# pca10059.net
KiCad netlist of a schematic drawn in Altium Designer
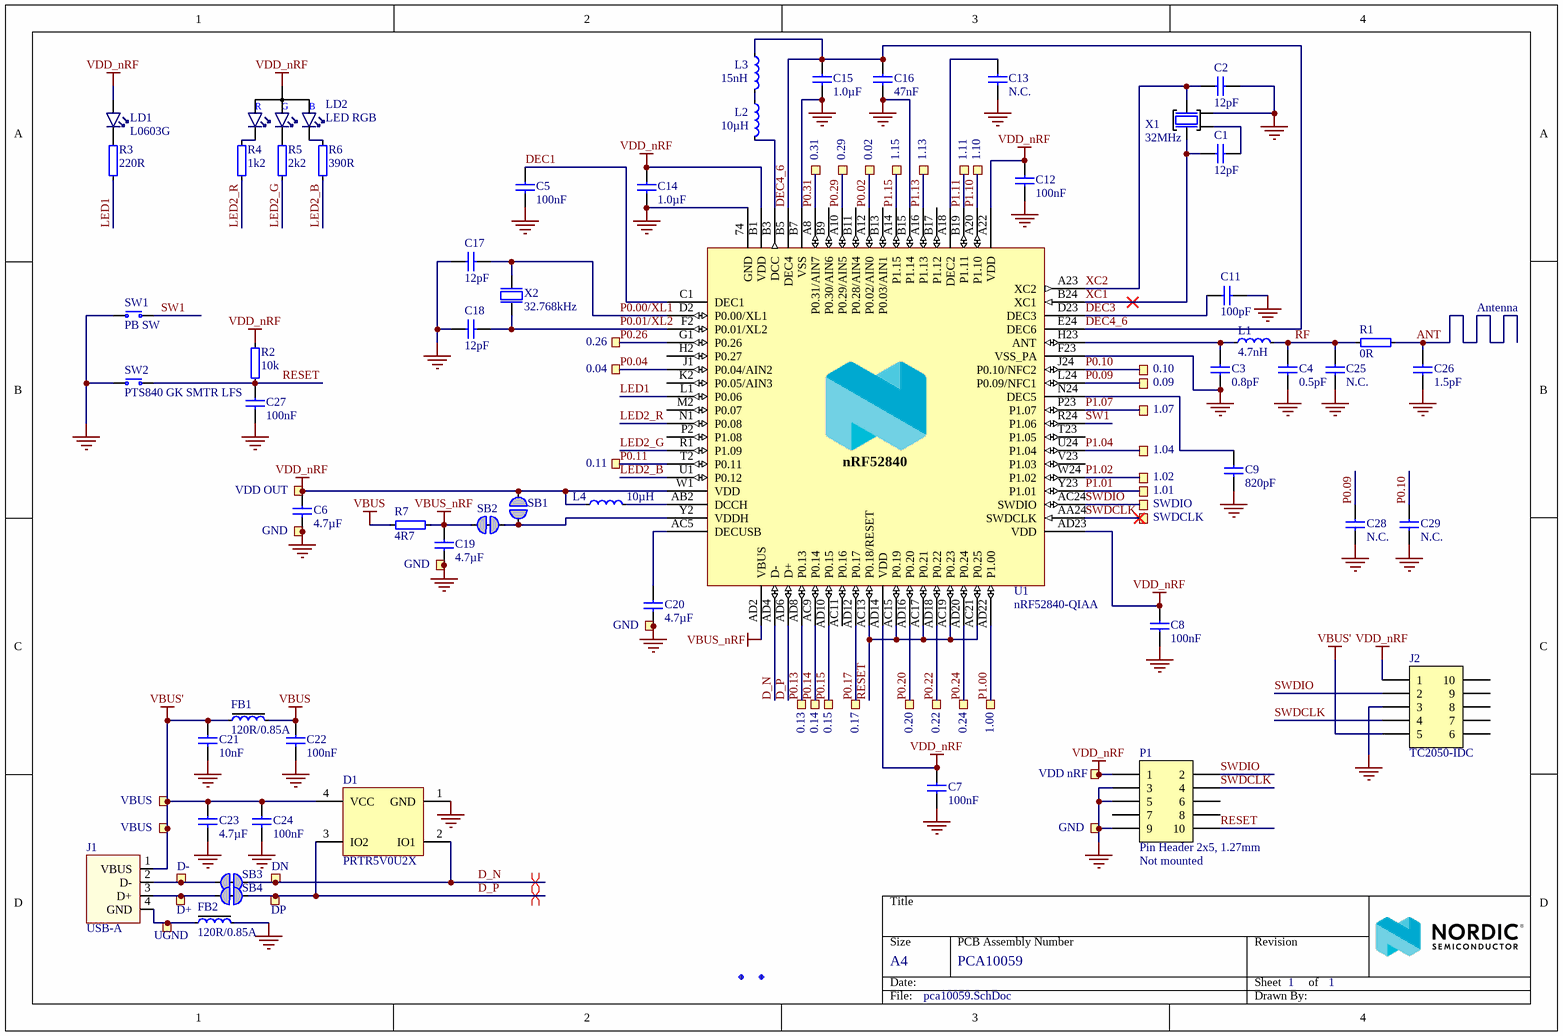
[diagram p0: pca10059.SchDoc]

(export (version "E")
  (design (tool "Eeschema 10.0.6"))
  (components
    (comp (ref "0.02")
      (value "CH")
      (footprint "Castellated_Hole_0.9mm")
      (description "Castellated Hole 0.9mm")
      (fields (field (name "MANUFACTURER") "N.A.") (field (name "AUTHOR") "rsk"))
      (libsource (lib "") (part "TESTPAD_2"))
    )
    (comp (ref "0.04")
      (value "Ø1.0mm,SMD")
      (footprint "TP_SMD_D1.0mm")
      (description "1.0mm circular SMD testpad")
      (fields
        (field (name "PART NUMBER") "TP_SMD_Ø1.0MM")
        (field (name "MANUFACTURER") "Nordic Semiconductor")
        (field (name "AUTHOR") "rsk")
      )
      (libsource (lib "AltiumLib") (part "TESTPAD"))
    )
    (comp (ref "0.09")
      (value "CH")
      (footprint "Castellated_Hole_0.9mm")
      (description "Castellated Hole 0.9mm")
      (fields (field (name "MANUFACTURER") "N.A.") (field (name "AUTHOR") "rsk"))
      (libsource (lib "") (part "TESTPAD_3"))
    )
    (comp (ref "0.10")
      (value "CH")
      (footprint "Castellated_Hole_0.9mm")
      (description "Castellated Hole 0.9mm")
      (fields (field (name "MANUFACTURER") "N.A.") (field (name "AUTHOR") "rsk"))
      (libsource (lib "") (part "TESTPAD_3"))
    )
    (comp (ref "0.11")
      (value "Ø1.0mm,SMD")
      (footprint "TP_SMD_D1.0mm")
      (description "1.0mm circular SMD testpad")
      (fields
        (field (name "PART NUMBER") "TP_SMD_Ø1.0MM")
        (field (name "MANUFACTURER") "Nordic Semiconductor")
        (field (name "AUTHOR") "rsk")
      )
      (libsource (lib "AltiumLib") (part "TESTPAD"))
    )
    (comp (ref "0.13")
      (value "CH")
      (footprint "Castellated_Hole_0.9mm")
      (description "Castellated Hole 0.9mm")
      (fields (field (name "MANUFACTURER") "N.A.") (field (name "AUTHOR") "rsk"))
      (libsource (lib "") (part "TESTPAD_1"))
    )
    (comp (ref "0.14")
      (value "Ø1.0mm,SMD")
      (footprint "TP_SMD_D1.0mm")
      (description "1.0mm circular SMD testpad")
      (fields
        (field (name "PART NUMBER") "TP_SMD_Ø1.0MM")
        (field (name "MANUFACTURER") "Nordic Semiconductor")
        (field (name "AUTHOR") "rsk")
      )
      (libsource (lib "") (part "TESTPAD_1"))
    )
    (comp (ref "0.15")
      (value "CH")
      (footprint "Castellated_Hole_0.9mm")
      (description "Castellated Hole 0.9mm")
      (fields (field (name "MANUFACTURER") "N.A.") (field (name "AUTHOR") "rsk"))
      (libsource (lib "") (part "TESTPAD_1"))
    )
    (comp (ref "0.17")
      (value "CH")
      (footprint "Castellated_Hole_0.9mm")
      (description "Castellated Hole 0.9mm")
      (fields (field (name "MANUFACTURER") "N.A.") (field (name "AUTHOR") "rsk"))
      (libsource (lib "") (part "TESTPAD_1"))
    )
    (comp (ref "0.20")
      (value "CH")
      (footprint "Castellated_Hole_0.9mm")
      (description "Castellated Hole 0.9mm")
      (fields (field (name "MANUFACTURER") "N.A.") (field (name "AUTHOR") "rsk"))
      (libsource (lib "") (part "TESTPAD_1"))
    )
    (comp (ref "0.22")
      (value "CH")
      (footprint "Castellated_Hole_0.9mm")
      (description "Castellated Hole 0.9mm")
      (fields (field (name "MANUFACTURER") "N.A.") (field (name "AUTHOR") "rsk"))
      (libsource (lib "") (part "TESTPAD_1"))
    )
    (comp (ref "0.24")
      (value "CH")
      (footprint "Castellated_Hole_0.9mm")
      (description "Castellated Hole 0.9mm")
      (fields (field (name "MANUFACTURER") "N.A.") (field (name "AUTHOR") "rsk"))
      (libsource (lib "") (part "TESTPAD_1"))
    )
    (comp (ref "0.26")
      (value "Ø1.0mm,SMD")
      (footprint "TP_SMD_D1.0mm")
      (description "1.0mm circular SMD testpad")
      (fields
        (field (name "PART NUMBER") "TP_SMD_Ø1.0MM")
        (field (name "MANUFACTURER") "Nordic Semiconductor")
        (field (name "AUTHOR") "rsk")
      )
      (libsource (lib "AltiumLib") (part "TESTPAD"))
    )
    (comp (ref "0.29")
      (value "CH")
      (footprint "Castellated_Hole_0.9mm")
      (description "Castellated Hole 0.9mm")
      (fields (field (name "MANUFACTURER") "N.A.") (field (name "AUTHOR") "rsk"))
      (libsource (lib "") (part "TESTPAD_2"))
    )
    (comp (ref "0.31")
      (value "CH")
      (footprint "Castellated_Hole_0.9mm")
      (description "Castellated Hole 0.9mm")
      (fields (field (name "MANUFACTURER") "N.A.") (field (name "AUTHOR") "rsk"))
      (libsource (lib "") (part "TESTPAD_2"))
    )
    (comp (ref "1.00")
      (value "CH")
      (footprint "Castellated_Hole_0.9mm")
      (description "Castellated Hole 0.9mm")
      (fields (field (name "MANUFACTURER") "N.A.") (field (name "AUTHOR") "rsk"))
      (libsource (lib "") (part "TESTPAD_1"))
    )
    (comp (ref "1.01")
      (value "Ø1.0mm,SMD")
      (footprint "TP_SMD_D1.0mm")
      (description "1.0mm circular SMD testpad")
      (fields
        (field (name "PART NUMBER") "TP_SMD_Ø1.0MM")
        (field (name "MANUFACTURER") "Nordic Semiconductor")
        (field (name "AUTHOR") "rsk")
      )
      (libsource (lib "") (part "TESTPAD_3"))
    )
    (comp (ref "1.02")
      (value "Ø1.0mm,SMD")
      (footprint "TP_SMD_D1.0mm")
      (description "1.0mm circular SMD testpad")
      (fields
        (field (name "PART NUMBER") "TP_SMD_Ø1.0MM")
        (field (name "MANUFACTURER") "Nordic Semiconductor")
        (field (name "AUTHOR") "rsk")
      )
      (libsource (lib "") (part "TESTPAD_3"))
    )
    (comp (ref "1.04")
      (value "Ø1.0mm,SMD")
      (footprint "TP_SMD_D1.0mm")
      (description "1.0mm circular SMD testpad")
      (fields
        (field (name "PART NUMBER") "TP_SMD_Ø1.0MM")
        (field (name "MANUFACTURER") "Nordic Semiconductor")
        (field (name "AUTHOR") "rsk")
      )
      (libsource (lib "") (part "TESTPAD_3"))
    )
    (comp (ref "1.07")
      (value "Ø1.0mm,SMD")
      (footprint "TP_SMD_D1.0mm")
      (description "1.0mm circular SMD testpad")
      (fields
        (field (name "PART NUMBER") "TP_SMD_Ø1.0MM")
        (field (name "MANUFACTURER") "Nordic Semiconductor")
        (field (name "AUTHOR") "rsk")
      )
      (libsource (lib "") (part "TESTPAD_3"))
    )
    (comp (ref "1.10")
      (value "CH")
      (footprint "Castellated_Hole_0.9mm")
      (description "Castellated Hole 0.9mm")
      (fields (field (name "MANUFACTURER") "N.A.") (field (name "AUTHOR") "rsk"))
      (libsource (lib "") (part "TESTPAD_2"))
    )
    (comp (ref "1.11")
      (value "Ø1.0mm,SMD")
      (footprint "TP_SMD_D1.0mm")
      (description "1.0mm circular SMD testpad")
      (fields
        (field (name "PART NUMBER") "TP_SMD_Ø1.0MM")
        (field (name "MANUFACTURER") "Nordic Semiconductor")
        (field (name "AUTHOR") "rsk")
      )
      (libsource (lib "") (part "TESTPAD_2"))
    )
    (comp (ref "1.13")
      (value "CH")
      (footprint "Castellated_Hole_0.9mm")
      (description "Castellated Hole 0.9mm")
      (fields (field (name "MANUFACTURER") "N.A.") (field (name "AUTHOR") "rsk"))
      (libsource (lib "") (part "TESTPAD_2"))
    )
    (comp (ref "1.15")
      (value "CH")
      (footprint "Castellated_Hole_0.9mm")
      (description "Castellated Hole 0.9mm")
      (fields (field (name "MANUFACTURER") "N.A.") (field (name "AUTHOR") "rsk"))
      (libsource (lib "") (part "TESTPAD_2"))
    )
    (comp (ref "C1")
      (value "12pF")
      (footprint "CAPC0603X03L_C")
      (description "Capacitor, NP0, ±2%")
      (fields
        (field (name "PART NUMBER") "C0201-12p")
        (field (name "MANUFACTURER") "N.A.")
        (field (name "AUTHOR") "rsk")
      )
      (libsource (lib "AltiumLib") (part "CAP"))
    )
    (comp (ref "C2")
      (value "12pF")
      (footprint "CAPC0603X03L_C")
      (description "Capacitor, NP0, ±2%")
      (fields
        (field (name "PART NUMBER") "C0201-12p")
        (field (name "MANUFACTURER") "N.A.")
        (field (name "AUTHOR") "rsk")
      )
      (libsource (lib "AltiumLib") (part "CAP"))
    )
    (comp (ref "C3")
      (value "0.8pF")
      (footprint "CAPC0603X03L_C")
      (description "Capacitor, NP0, ±0.05pF, 50V")
      (fields
        (field (name "PART NUMBER") "C0201-0.8p")
        (field (name "MANUFACTURER") "Murata")
        (field (name "AUTHOR") "rsk")
      )
      (libsource (lib "AltiumLib") (part "CAP"))
    )
    (comp (ref "C4")
      (value "0.5pF")
      (footprint "CAPC0603X03L_C")
      (description "Capacitor, NP0, ±0.05pF")
      (fields
        (field (name "PART NUMBER") "C0201-0.5p")
        (field (name "MANUFACTURER") "N.A.")
        (field (name "AUTHOR") "rsk")
      )
      (libsource (lib "AltiumLib") (part "CAP"))
    )
    (comp (ref "C5")
      (value "100nF")
      (footprint "CAPC0603X03L_C")
      (description "Capacitor, X5R, ±10%")
      (fields
        (field (name "PART NUMBER") "C0201-100n")
        (field (name "MANUFACTURER") "N.A.")
        (field (name "AUTHOR") "rsk")
      )
      (libsource (lib "AltiumLib") (part "CAP"))
    )
    (comp (ref "C6")
      (value "4.7µF")
      (footprint "CAPC1608X06L")
      (description "Capacitor, X5R, ±10%")
      (fields
        (field (name "PART NUMBER") "C0603-4µ7")
        (field (name "MANUFACTURER") "N.A.")
        (field (name "AUTHOR") "rsk")
      )
      (libsource (lib "AltiumLib") (part "CAP"))
    )
    (comp (ref "C7")
      (value "100nF")
      (footprint "CAPC0603X03L_C")
      (description "Capacitor, X5R, ±10%")
      (fields
        (field (name "PART NUMBER") "C0201-100n")
        (field (name "MANUFACTURER") "N.A.")
        (field (name "AUTHOR") "rsk")
      )
      (libsource (lib "AltiumLib") (part "CAP"))
    )
    (comp (ref "C8")
      (value "100nF")
      (footprint "CAPC0603X03L_C")
      (description "Capacitor, X5R, ±10%")
      (fields
        (field (name "PART NUMBER") "C0201-100n")
        (field (name "MANUFACTURER") "N.A.")
        (field (name "AUTHOR") "rsk")
      )
      (libsource (lib "AltiumLib") (part "CAP"))
    )
    (comp (ref "C9")
      (value "820pF")
      (footprint "CAPC0603X03L_C")
      (description "Capacitor, X7R, ±10%")
      (fields
        (field (name "PART NUMBER") "C0201-820p")
        (field (name "MANUFACTURER") "N.A.")
        (field (name "AUTHOR") "rsk")
      )
      (libsource (lib "AltiumLib") (part "CAP"))
    )
    (comp (ref "C11")
      (value "100pF")
      (footprint "CAPC0603X03L_C")
      (description "Capacitor, NP0, ±2%, 25V")
      (fields
        (field (name "PART NUMBER") "C0201-100p")
        (field (name "MANUFACTURER") "Murata")
        (field (name "AUTHOR") "rsk")
      )
      (libsource (lib "AltiumLib") (part "CAP"))
    )
    (comp (ref "C12")
      (value "100nF")
      (footprint "CAPC0603X03L_C")
      (description "Capacitor, X5R, ±10%")
      (fields
        (field (name "PART NUMBER") "C0201-100n")
        (field (name "MANUFACTURER") "N.A.")
        (field (name "AUTHOR") "rsk")
      )
      (libsource (lib "AltiumLib") (part "CAP"))
    )
    (comp (ref "C13")
      (value "N.C.")
      (footprint "CAPC0603X03L_C_NC")
      (description "Not mounted")
      (fields
        (field (name "PART NUMBER") "C0201-N.C.")
        (field (name "MANUFACTURER") "N.A.")
        (field (name "AUTHOR") "rsk")
      )
      (libsource (lib "AltiumLib") (part "CAP"))
    )
    (comp (ref "C14")
      (value "1.0µF")
      (footprint "CAPC1608X06L")
      (description "Capacitor, X7R, ±10%")
      (fields
        (field (name "PART NUMBER") "C0603-1µ0")
        (field (name "MANUFACTURER") "N.A.")
        (field (name "AUTHOR") "rsk")
      )
      (libsource (lib "AltiumLib") (part "CAP"))
    )
    (comp (ref "C15")
      (value "1.0µF")
      (footprint "CAPC1608X06L")
      (description "Capacitor, X7R, ±10%")
      (fields
        (field (name "PART NUMBER") "C0603-1µ0")
        (field (name "MANUFACTURER") "N.A.")
        (field (name "AUTHOR") "rsk")
      )
      (libsource (lib "AltiumLib") (part "CAP"))
    )
    (comp (ref "C16")
      (value "47nF")
      (footprint "CAPC0603X03L_C")
      (description "Capacitor, X5R, ±10%")
      (fields
        (field (name "PART NUMBER") "C0201-47n")
        (field (name "MANUFACTURER") "N.A.")
        (field (name "AUTHOR") "rsk")
      )
      (libsource (lib "AltiumLib") (part "CAP"))
    )
    (comp (ref "C17")
      (value "12pF")
      (footprint "CAPC0603X03L_C")
      (description "Capacitor, NP0, ±2%")
      (fields
        (field (name "PART NUMBER") "C0201-12p")
        (field (name "MANUFACTURER") "N.A.")
        (field (name "AUTHOR") "rsk")
      )
      (libsource (lib "AltiumLib") (part "CAP"))
    )
    (comp (ref "C18")
      (value "12pF")
      (footprint "CAPC0603X03L_C")
      (description "Capacitor, NP0, ±2%")
      (fields
        (field (name "PART NUMBER") "C0201-12p")
        (field (name "MANUFACTURER") "N.A.")
        (field (name "AUTHOR") "rsk")
      )
      (libsource (lib "AltiumLib") (part "CAP"))
    )
    (comp (ref "C19")
      (value "4.7µF")
      (footprint "CAPC1005X04L")
      (description "Capacitor, X5R, ±20%")
      (fields
        (field (name "PART NUMBER") "C0402-4µ7")
        (field (name "MANUFACTURER") "N.A.")
        (field (name "AUTHOR") "rsk")
      )
      (libsource (lib "AltiumLib") (part "CAP"))
    )
    (comp (ref "C20")
      (value "4.7µF")
      (footprint "CAPC1608X06L")
      (description "Capacitor, X5R, ±10%")
      (fields
        (field (name "PART NUMBER") "C0603-4µ7")
        (field (name "MANUFACTURER") "N.A.")
        (field (name "AUTHOR") "rsk")
      )
      (libsource (lib "AltiumLib") (part "CAP"))
    )
    (comp (ref "C21")
      (value "10nF")
      (footprint "CAPC0603X03L_C")
      (description "Capacitor, X7R, ±10%")
      (fields
        (field (name "PART NUMBER") "C0201-10n")
        (field (name "MANUFACTURER") "N.A.")
        (field (name "AUTHOR") "rsk")
      )
      (libsource (lib "AltiumLib") (part "CAP"))
    )
    (comp (ref "C22")
      (value "100nF")
      (footprint "CAPC0603X03L_C")
      (description "Capacitor, X5R, ±10%")
      (fields
        (field (name "PART NUMBER") "C0201-100n")
        (field (name "MANUFACTURER") "N.A.")
        (field (name "AUTHOR") "rsk")
      )
      (libsource (lib "AltiumLib") (part "CAP"))
    )
    (comp (ref "C23")
      (value "4.7µF")
      (footprint "CAPC1005X04L")
      (description "Capacitor, X5R, ±20%")
      (fields
        (field (name "PART NUMBER") "C0402-4µ7")
        (field (name "MANUFACTURER") "N.A.")
        (field (name "AUTHOR") "rsk")
      )
      (libsource (lib "AltiumLib") (part "CAP"))
    )
    (comp (ref "C24")
      (value "100nF")
      (footprint "CAPC0603X03L_C")
      (description "Capacitor, X5R, ±10%")
      (fields
        (field (name "PART NUMBER") "C0201-100n")
        (field (name "MANUFACTURER") "N.A.")
        (field (name "AUTHOR") "rsk")
      )
      (libsource (lib "AltiumLib") (part "CAP"))
    )
    (comp (ref "C25")
      (value "N.C.")
      (footprint "CAPC0603X03L_C_NC")
      (description "Not mounted")
      (fields
        (field (name "PART NUMBER") "C0201-N.C.")
        (field (name "MANUFACTURER") "N.A.")
        (field (name "AUTHOR") "rsk")
      )
      (libsource (lib "AltiumLib") (part "CAP"))
    )
    (comp (ref "C26")
      (value "1.5pF")
      (footprint "CAPC0603X03L_C")
      (description "Capacitor, NP0, ±0.1pF")
      (fields
        (field (name "PART NUMBER") "C0201-1.5p")
        (field (name "MANUFACTURER") "N.A.")
        (field (name "AUTHOR") "rsk")
      )
      (libsource (lib "AltiumLib") (part "CAP"))
    )
    (comp (ref "C27")
      (value "100nF")
      (footprint "CAPC0603X03L_C")
      (description "Capacitor, X5R, ±10%")
      (fields
        (field (name "PART NUMBER") "C0201-100n")
        (field (name "MANUFACTURER") "N.A.")
        (field (name "AUTHOR") "rsk")
      )
      (libsource (lib "AltiumLib") (part "CAP"))
    )
    (comp (ref "C28")
      (value "N.C.")
      (footprint "CAPC1005X04L_NC")
      (description "Not mounted")
      (fields
        (field (name "PART NUMBER") "C0402-N.C.")
        (field (name "MANUFACTURER") "N.A.")
        (field (name "AUTHOR") "rsk")
      )
      (libsource (lib "AltiumLib") (part "CAP"))
    )
    (comp (ref "C29")
      (value "N.C.")
      (footprint "CAPC1005X04L_NC")
      (description "Not mounted")
      (fields
        (field (name "PART NUMBER") "C0402-N.C.")
        (field (name "MANUFACTURER") "N.A.")
        (field (name "AUTHOR") "rsk")
      )
      (libsource (lib "AltiumLib") (part "CAP"))
    )
    (comp (ref "D+")
      (value "Ø1.0mm,SMD")
      (footprint "TP_SMD_D1.0mm")
      (description "1.0mm circular SMD testpad")
      (fields
        (field (name "PART NUMBER") "TP_SMD_Ø1.0MM")
        (field (name "MANUFACTURER") "Nordic Semiconductor")
        (field (name "AUTHOR") "rsk")
      )
      (libsource (lib "") (part "TESTPAD_1"))
    )
    (comp (ref "D-")
      (value "Ø1.0mm,SMD")
      (footprint "TP_SMD_D1.0mm")
      (description "1.0mm circular SMD testpad")
      (fields
        (field (name "PART NUMBER") "TP_SMD_Ø1.0MM")
        (field (name "MANUFACTURER") "Nordic Semiconductor")
        (field (name "AUTHOR") "rsk")
      )
      (libsource (lib "") (part "TESTPAD_2"))
    )
    (comp (ref "D1")
      (value "PRTR5V0U2X")
      (footprint "SOT190P230X110-4L")
      (description "Ultra low capacitance double rail-to-rail ESD protection diode")
      (fields (field (name "MANUFACTURER") "NXP Semiconductors") (field (name "AUTHOR") "rsk"))
      (libsource (lib "AltiumLib") (part "PRTR5V0U2X"))
    )
    (comp (ref "DN")
      (value "Ø1.0mm,SMD")
      (footprint "TP_SMD_D1.0mm")
      (description "1.0mm circular SMD testpad")
      (fields
        (field (name "PART NUMBER") "TP_SMD_Ø1.0MM")
        (field (name "MANUFACTURER") "Nordic Semiconductor")
        (field (name "AUTHOR") "rsk")
      )
      (libsource (lib "") (part "TESTPAD_2"))
    )
    (comp (ref "DP")
      (value "Ø1.0mm,SMD")
      (footprint "TP_SMD_D1.0mm")
      (description "1.0mm circular SMD testpad")
      (fields
        (field (name "PART NUMBER") "TP_SMD_Ø1.0MM")
        (field (name "MANUFACTURER") "Nordic Semiconductor")
        (field (name "AUTHOR") "rsk")
      )
      (libsource (lib "") (part "TESTPAD_1"))
    )
    (comp (ref "FB1")
      (value "120R/0.85A")
      (footprint "INDC0603X03L_C")
      (description "Ferrite Bead, 120 Ohm @ 100MHz, 850mA, 150 mOhm Max")
      (fields
        (field (name "PART NUMBER") "FB0201-120R@100M-850mA")
        (field (name "MANUFACTURER") "Taiyo Yuden")
        (field (name "AUTHOR") "rsk")
      )
      (libsource (lib "AltiumLib") (part "IND_F"))
    )
    (comp (ref "FB2")
      (value "120R/0.85A")
      (footprint "INDC0603X03L_C")
      (description "Ferrite Bead, 120 Ohm @ 100MHz, 850mA, 150 mOhm Max")
      (fields
        (field (name "PART NUMBER") "FB0201-120R@100M-850mA")
        (field (name "MANUFACTURER") "Taiyo Yuden")
        (field (name "AUTHOR") "rsk")
      )
      (libsource (lib "AltiumLib") (part "IND_F"))
    )
    (comp (ref "Fid1")
      (value "Fiducial mark")
      (footprint "Fiducial_Square")
      (description "Fiducial Mark")
      (fields
        (field (name "PART NUMBER") "Fid-Mark-Square")
        (field (name "MANUFACTURER") "N.A.")
        (field (name "AUTHOR") "rsk")
      )
      (libsource (lib "AltiumLib") (part "Fiducial"))
    )
    (comp (ref "Fid2")
      (value "Fiducial mark")
      (footprint "Fiducial")
      (description "Fiducial Mark")
      (fields
        (field (name "PART NUMBER") "Fid-Mark")
        (field (name "MANUFACTURER") "N.A.")
        (field (name "AUTHOR") "rsk")
      )
      (libsource (lib "AltiumLib") (part "Fiducial"))
    )
    (comp (ref "GND1")
      (value "GND")
      (footprint "Castellated_Hole_0.9mm")
      (description "Castellated Hole 0.9mm")
      (fields (field (name "MANUFACTURER") "N.A.") (field (name "AUTHOR") "rsk"))
      (libsource (lib "AltiumLib") (part "TESTPAD"))
    )
    (comp (ref "GND2")
      (value "GND")
      (footprint "Castellated_Hole_0.9mm_S")
      (description "Castellated Hole 0.9mm")
      (fields
        (field (name "PART NUMBER") "Castellated Hole 0.9mm_S")
        (field (name "MANUFACTURER") "N.A.")
        (field (name "AUTHOR") "rsk")
      )
      (libsource (lib "AltiumLib") (part "TESTPAD"))
    )
    (comp (ref "GND3")
      (value "GND")
      (footprint "Castellated_Hole_0.9mm_S")
      (description "Castellated Hole 0.9mm")
      (fields
        (field (name "PART NUMBER") "Castellated Hole 0.9mm_S")
        (field (name "MANUFACTURER") "N.A.")
        (field (name "AUTHOR") "rsk")
      )
      (libsource (lib "AltiumLib") (part "TESTPAD"))
    )
    (comp (ref "GND4")
      (value "GND")
      (footprint "TP_SMD_D1.0mm")
      (description "1.0mm circular SMD testpad")
      (fields
        (field (name "PART NUMBER") "TP_SMD_Ø1.0MM")
        (field (name "MANUFACTURER") "Nordic Semiconductor")
        (field (name "AUTHOR") "rsk")
      )
      (libsource (lib "AltiumLib") (part "TESTPAD"))
    )
    (comp (ref "J1")
      (value "USB-A")
      (footprint "USB-A-PCB")
      (description "USB-A PCB footprint")
      (fields
        (field (name "PART NUMBER") "USB-A-PCB")
        (field (name "MANUFACTURER") "N.A.")
        (field (name "AUTHOR") "rsk")
      )
      (libsource (lib "AltiumLib") (part "USB-PCB-A"))
    )
    (comp (ref "J2")
      (value "TC2050-IDC")
      (footprint "TC2050-IDC-NLFP")
      (description "CBL PLUG-OF-NAILS 10-PIN")
      (fields
        (field (name "PART NUMBER") "TC2050-IDC-NLFP")
        (field (name "MANUFACTURER") "Tag-Connect LLC")
        (field (name "AUTHOR") "rsk")
      )
      (libsource (lib "AltiumLib") (part "CONN-2x5_var2_No_BOM"))
    )
    (comp (ref "L1")
      (value "4.7nH")
      (footprint "INDC0603X03L_C")
      (description "Inductor, 350mA, ±3%")
      (fields
        (field (name "PART NUMBER") "L0201-4n7")
        (field (name "MANUFACTURER") "Murata")
        (field (name "AUTHOR") "rsk")
      )
      (libsource (lib "AltiumLib") (part "IND"))
    )
    (comp (ref "L2")
      (value "10µH")
      (footprint "INDC1608X06L")
      (description "Inductor, 80mA, ±10%")
      (fields
        (field (name "PART NUMBER") "L0603-10µ")
        (field (name "MANUFACTURER") "Taiyo Yuden")
        (field (name "AUTHOR") "rsk")
      )
      (libsource (lib "AltiumLib") (part "IND"))
    )
    (comp (ref "L3")
      (value "15nH")
      (footprint "INDC1005X04L")
      (description "Inductor, 320mA, ±5%")
      (fields
        (field (name "PART NUMBER") "L0402-15n")
        (field (name "MANUFACTURER") "Taiyo Yuden")
        (field (name "AUTHOR") "rsk")
      )
      (libsource (lib "AltiumLib") (part "IND"))
    )
    (comp (ref "L4")
      (value "10µH")
      (footprint "INDC1608X06L")
      (description "Inductor, 80mA, ±10%")
      (fields
        (field (name "PART NUMBER") "L0603-10µ")
        (field (name "MANUFACTURER") "Taiyo Yuden")
        (field (name "AUTHOR") "rsk")
      )
      (libsource (lib "AltiumLib") (part "IND"))
    )
    (comp (ref "LD1")
      (value "L0603G")
      (footprint "LED_0603_G")
      (description "LED, Green, 0603, 573nm, Vf=2.0V, 24mcd, - 40 to +85°C")
      (fields
        (field (name "PART NUMBER") "VS 25C7M5")
        (field (name "MANUFACTURER") "Victory Electronics")
        (field (name "AUTHOR") "rsk")
      )
      (libsource (lib "AltiumLib") (part "D{colon}LED"))
    )
    (comp (ref "LD2")
      (value "LED RGB")
      (footprint "LED_RGB_0603")
      (description "RGB LED 1.60 mm x 0.80 mm SMD")
      (fields
        (field (name "PART NUMBER") "APHF1608LSEEQBDZGKC")
        (field (name "MANUFACTURER") "Kingbright Company LLC")
        (field (name "AUTHOR") "rsk")
      )
      (libsource (lib "AltiumLib") (part "D{colon}LED_RGB"))
    )
    (comp (ref "P1")
      (value "Pin Header 2x5, 1.27mm")
      (footprint "HDR_2x5-SMD-1.27mm-NC")
      (description "Pin Header 2x5, 1.27mm (50mil), SMD, Keying Shroud")
      (fields
        (field (name "PART NUMBER") "Pin Header 2x5 SMD, 1.27mm, KS, N.C.")
        (field (name "ASSEMBLY") "Not mounted")
        (field (name "MANUFACTURER") "W-CON")
        (field (name "AUTHOR") "rsk")
      )
      (libsource (lib "AltiumLib") (part "CONN-2x5"))
    )
    (comp (ref "R1")
      (value "0R")
      (footprint "RESC0603X03L_C")
      (description "Resistor, ±5%, 0.05W")
      (fields
        (field (name "PART NUMBER") "R0201-0R")
        (field (name "MANUFACTURER") "N.A.")
        (field (name "AUTHOR") "rsk")
      )
      (libsource (lib "AltiumLib") (part "RES"))
    )
    (comp (ref "R2")
      (value "10k")
      (footprint "RESC0603X03L_C")
      (description "Resistor, ±1%, 0.05W")
      (fields
        (field (name "PART NUMBER") "R0201-10k")
        (field (name "MANUFACTURER") "N.A.")
        (field (name "AUTHOR") "rsk")
      )
      (libsource (lib "AltiumLib") (part "RES"))
    )
    (comp (ref "R3")
      (value "220R")
      (footprint "RESC0603X03L_C")
      (description "Resistor, ±1%, 0.05W")
      (fields
        (field (name "PART NUMBER") "R0201-220")
        (field (name "MANUFACTURER") "N.A.")
        (field (name "AUTHOR") "rsk")
      )
      (libsource (lib "AltiumLib") (part "RES"))
    )
    (comp (ref "R4")
      (value "1k2")
      (footprint "RESC0603X03L_C")
      (description "Resistor, ±1%, 0.05W")
      (fields
        (field (name "PART NUMBER") "R0201-1k2")
        (field (name "MANUFACTURER") "N.A.")
        (field (name "AUTHOR") "rsk")
      )
      (libsource (lib "AltiumLib") (part "RES"))
    )
    (comp (ref "R5")
      (value "2k2")
      (footprint "RESC0603X03L_C")
      (description "Resistor, ±1%, 0.05W")
      (fields
        (field (name "PART NUMBER") "R0201-2k2")
        (field (name "MANUFACTURER") "N.A.")
        (field (name "AUTHOR") "rsk")
      )
      (libsource (lib "AltiumLib") (part "RES"))
    )
    (comp (ref "R6")
      (value "390R")
      (footprint "RESC0603X03L_C")
      (description "Resistor, ±1%, 0.05W")
      (fields
        (field (name "PART NUMBER") "R0201-390")
        (field (name "MANUFACTURER") "N.A.")
        (field (name "AUTHOR") "rsk")
      )
      (libsource (lib "AltiumLib") (part "RES"))
    )
    (comp (ref "R7")
      (value "4R7")
      (footprint "RESC0603X03L_C")
      (description "Resistor, ±1%, 0.05W")
      (fields
        (field (name "PART NUMBER") "R0201-4R7")
        (field (name "MANUFACTURER") "N.A.")
        (field (name "AUTHOR") "rsk")
      )
      (libsource (lib "AltiumLib") (part "RES"))
    )
    (comp (ref "SB1")
      (value "Solderbridge")
      (footprint "Solderbridge")
      (fields (field (name "MANUFACTURER") "N.A.") (field (name "AUTHOR") "rsk"))
      (libsource (lib "AltiumLib") (part "SOLDERBRIDGE"))
    )
    (comp (ref "SB2")
      (value "Solderbridge")
      (footprint "Solderbridge_Shorted")
      (description "Shorted Solderbridge")
      (fields
        (field (name "PART NUMBER") "Solderbridge Shorted")
        (field (name "MANUFACTURER") "N.A.")
        (field (name "AUTHOR") "rsk")
      )
      (libsource (lib "AltiumLib") (part "SOLDERBRIDGE_SHORTED"))
    )
    (comp (ref "SB3")
      (value "Solderbridge")
      (footprint "Solderbridge_Shorted")
      (description "Shorted Solderbridge")
      (fields
        (field (name "PART NUMBER") "Solderbridge Shorted")
        (field (name "MANUFACTURER") "N.A.")
        (field (name "AUTHOR") "rsk")
      )
      (libsource (lib "AltiumLib") (part "SOLDERBRIDGE_SHORTED"))
    )
    (comp (ref "SB4")
      (value "Solderbridge")
      (footprint "Solderbridge_Shorted")
      (description "Shorted Solderbridge")
      (fields
        (field (name "PART NUMBER") "Solderbridge Shorted")
        (field (name "MANUFACTURER") "N.A.")
        (field (name "AUTHOR") "rsk")
      )
      (libsource (lib "AltiumLib") (part "SOLDERBRIDGE_SHORTED"))
    )
    (comp (ref "SW1")
      (value "PB SW")
      (footprint "C&K_PTS810")
      (description "Tactile Switch, SPNO, SMD, 260gf, 4.2x3.2x2.5mm")
      (fields
        (field (name "PART NUMBER") "PTS810 SJK 250 SMTR LFS")
        (field (name "MANUFACTURER") "C&K")
        (field (name "AUTHOR") "rsk")
      )
      (libsource (lib "AltiumLib") (part "SW-PB"))
    )
    (comp (ref "SW2")
      (value "PTS840 GK SMTR LFS")
      (footprint "EVQP7A_J_B_K")
      (description "Microminiature SMT Switch, Side Actuated")
      (fields (field (name "MANUFACTURER") "C&K") (field (name "AUTHOR") "rsk"))
      (libsource (lib "AltiumLib") (part "SW-PB"))
    )
    (comp (ref "SWDCLK")
      (value "CH")
      (footprint "Castellated_Hole_0.9mm_D")
      (description "Castellated Hole 0.9mm")
      (fields
        (field (name "PART NUMBER") "Castellated Hole 0.9mm_D")
        (field (name "MANUFACTURER") "N.A.")
        (field (name "AUTHOR") "rsk")
      )
      (libsource (lib "") (part "TESTPAD_3"))
    )
    (comp (ref "SWDIO")
      (value "CH")
      (footprint "Castellated_Hole_0.9mm_D")
      (description "Castellated Hole 0.9mm")
      (fields
        (field (name "PART NUMBER") "Castellated Hole 0.9mm_D")
        (field (name "MANUFACTURER") "N.A.")
        (field (name "AUTHOR") "rsk")
      )
      (libsource (lib "") (part "TESTPAD_3"))
    )
    (comp (ref "U1")
      (value "nRF52840-QIAA")
      (footprint "AQFN50P700X700X85_HS-74N")
      (description "Multi-protocol Bluetooth Low Energy, IEEE 802.15.4, ANT and 2.4GHz proprietary system-on-chip")
      (fields
        (field (name "PART NUMBER") "nRF52840-QIAAF0")
        (field (name "MANUFACTURER") "Nordic Semiconductor")
        (field (name "AUTHOR") "hany")
      )
      (libsource (lib "AltiumLib") (part "nRF52840_QIAA"))
    )
    (comp (ref "UGND")
      (value "Ø1.0mm,SMD")
      (footprint "TP_SMD_D1.0mm")
      (description "1.0mm circular SMD testpad")
      (fields
        (field (name "PART NUMBER") "TP_SMD_Ø1.0MM")
        (field (name "MANUFACTURER") "Nordic Semiconductor")
        (field (name "AUTHOR") "rsk")
      )
      (libsource (lib "") (part "TESTPAD_1"))
    )
    (comp (ref "VBUS1")
      (value "VBUS")
      (footprint "Castellated_Hole_0.9mm")
      (description "Castellated Hole 0.9mm")
      (fields (field (name "MANUFACTURER") "N.A.") (field (name "AUTHOR") "rsk"))
      (libsource (lib "AltiumLib") (part "TESTPAD"))
    )
    (comp (ref "VBUS2")
      (value "VBUS")
      (footprint "TP_SMD_D1.0mm")
      (description "1.0mm circular SMD testpad")
      (fields
        (field (name "PART NUMBER") "TP_SMD_Ø1.0MM")
        (field (name "MANUFACTURER") "Nordic Semiconductor")
        (field (name "AUTHOR") "rsk")
      )
      (libsource (lib "AltiumLib") (part "TESTPAD"))
    )
    (comp (ref "VDD nRF")
      (value "Ø1.0mm,SMD")
      (footprint "TP_SMD_D1.0mm")
      (description "1.0mm circular SMD testpad")
      (fields
        (field (name "PART NUMBER") "TP_SMD_Ø1.0MM")
        (field (name "MANUFACTURER") "Nordic Semiconductor")
        (field (name "AUTHOR") "rsk")
      )
      (libsource (lib "AltiumLib") (part "TESTPAD"))
    )
    (comp (ref "VDD OUT")
      (value "CH")
      (footprint "Castellated_Hole_0.9mm")
      (description "Castellated Hole 0.9mm")
      (fields (field (name "MANUFACTURER") "N.A.") (field (name "AUTHOR") "rsk"))
      (libsource (lib "AltiumLib") (part "TESTPAD"))
    )
    (comp (ref "X1")
      (value "32MHz")
      (footprint "BT-XTAL_2016")
      (description "XTAL SMD 2016, 32MHz, Cl=8pF, Tol: ±10ppm, Stab: ±10ppm")
      (fields
        (field (name "PART NUMBER") "XTAL_SMD2016_32MHz_8pF_Murata")
        (field (name "MANUFACTURER") "Murata")
        (field (name "AUTHOR") "rsk")
      )
      (libsource (lib "AltiumLib") (part "XTAL_4-pin"))
    )
    (comp (ref "X2")
      (value "32.768kHz")
      (footprint "XTAL_2012")
      (description "XTAL SMD 2012, 32.768kHz, 9pF, ±20ppm")
      (fields
        (field (name "PART NUMBER") "XTAL_SMD2012_32.768kHz_9pF_Seiko")
        (field (name "MANUFACTURER") "Seiko Instruments")
        (field (name "AUTHOR") "rsk")
      )
      (libsource (lib "AltiumLib") (part "XTAL_2-pin"))
    )
  )
  (nets
    (net (code "1") (name "/ANT") (class "Default")
      (node (ref "C26") (pin "2") (pinfunction "2_2") (pintype "passive"))
      (node (ref "R1") (pin "2") (pinfunction "2_2") (pintype "passive"))
    )
    (net (code "2") (name "/DEC1") (class "Default")
      (node (ref "C5") (pin "1") (pinfunction "1_1") (pintype "passive"))
      (node (ref "U1") (pin "C1") (pinfunction "DEC1_C1") (pintype "power_in"))
    )
    (net (code "3") (name "/DEC3") (class "Default")
      (node (ref "C11") (pin "1") (pinfunction "1_1") (pintype "passive"))
      (node (ref "U1") (pin "D23") (pinfunction "DEC3_D23") (pintype "power_in"))
    )
    (net (code "4") (name "/DEC4_6") (class "Default")
      (node (ref "C15") (pin "2") (pinfunction "2_2") (pintype "passive"))
      (node (ref "C16") (pin "1") (pinfunction "1_1") (pintype "passive"))
      (node (ref "L3") (pin "1") (pinfunction "1_1") (pintype "passive"))
      (node (ref "U1") (pin "B5") (pinfunction "DEC4_B5") (pintype "power_in"))
      (node (ref "U1") (pin "E24") (pinfunction "DEC6_E24") (pintype "power_in"))
    )
    (net (code "5") (name "/D_N") (class "Default")
      (node (ref "D1") (pin "2") (pinfunction "IO1_2") (pintype "passive"))
      (node (ref "DN") (pin "1") (pinfunction "1_1") (pintype "passive"))
      (node (ref "SB3") (pin "1") (pinfunction "0_1") (pintype "passive"))
      (node (ref "U1") (pin "AD4") (pinfunction "D-_AD4") (pintype "bidirectional"))
    )
    (net (code "6") (name "/D_P") (class "Default")
      (node (ref "D1") (pin "3") (pinfunction "IO2_3") (pintype "passive"))
      (node (ref "DP") (pin "1") (pinfunction "1_1") (pintype "passive"))
      (node (ref "SB4") (pin "1") (pinfunction "0_1") (pintype "passive"))
      (node (ref "U1") (pin "AD6") (pinfunction "D+_AD6") (pintype "bidirectional"))
    )
    (net (code "7") (name "/LED1") (class "Default")
      (node (ref "R3") (pin "1") (pinfunction "1_1") (pintype "passive"))
      (node (ref "U1") (pin "L1") (pinfunction "P0.06_L1") (pintype "bidirectional"))
    )
    (net (code "8") (name "/LED2_B") (class "Default")
      (node (ref "R6") (pin "1") (pinfunction "1_1") (pintype "passive"))
      (node (ref "U1") (pin "U1") (pinfunction "P0.12_U1") (pintype "bidirectional"))
    )
    (net (code "9") (name "/LED2_G") (class "Default")
      (node (ref "R5") (pin "1") (pinfunction "1_1") (pintype "passive"))
      (node (ref "U1") (pin "R1") (pinfunction "P1.09_R1") (pintype "bidirectional"))
    )
    (net (code "10") (name "/LED2_R") (class "Default")
      (node (ref "R4") (pin "1") (pinfunction "1_1") (pintype "passive"))
      (node (ref "U1") (pin "N1") (pinfunction "P0.08_N1") (pintype "bidirectional"))
    )
    (net (code "11") (name "/P0.00{slash}XL1") (class "Default")
      (node (ref "C17") (pin "1") (pinfunction "1_1") (pintype "passive"))
      (node (ref "U1") (pin "D2") (pinfunction "P0.00/XL1_D2") (pintype "bidirectional"))
      (node (ref "X2") (pin "1") (pinfunction "inp_1") (pintype "passive"))
    )
    (net (code "12") (name "/P0.01{slash}XL2") (class "Default")
      (node (ref "C18") (pin "1") (pinfunction "1_1") (pintype "passive"))
      (node (ref "U1") (pin "F2") (pinfunction "P0.01/XL2_F2") (pintype "bidirectional"))
      (node (ref "X2") (pin "2") (pinfunction "out_2") (pintype "passive"))
    )
    (net (code "13") (name "/P0.02") (class "Default")
      (node (ref "0.02") (pin "1") (pinfunction "1_1") (pintype "passive"))
      (node (ref "U1") (pin "A12") (pinfunction "P0.02/AIN0_A12") (pintype "bidirectional"))
    )
    (net (code "14") (name "/P0.04") (class "Default")
      (node (ref "0.04") (pin "1") (pinfunction "1_1") (pintype "passive"))
      (node (ref "U1") (pin "J1") (pinfunction "P0.04/AIN2_J1") (pintype "bidirectional"))
    )
    (net (code "15") (name "/P0.09") (class "Default")
      (node (ref "0.09") (pin "1") (pinfunction "1_1") (pintype "passive"))
      (node (ref "C28") (pin "2") (pinfunction "2_2") (pintype "passive"))
      (node (ref "U1") (pin "L24") (pinfunction "P0.09/NFC1_L24") (pintype "bidirectional"))
    )
    (net (code "16") (name "/P0.10") (class "Default")
      (node (ref "0.10") (pin "1") (pinfunction "1_1") (pintype "passive"))
      (node (ref "C29") (pin "1") (pinfunction "1_1") (pintype "passive"))
      (node (ref "U1") (pin "J24") (pinfunction "P0.10/NFC2_J24") (pintype "bidirectional"))
    )
    (net (code "17") (name "/P0.11") (class "Default")
      (node (ref "0.11") (pin "1") (pinfunction "1_1") (pintype "passive"))
      (node (ref "U1") (pin "T2") (pinfunction "P0.11_T2") (pintype "bidirectional"))
    )
    (net (code "18") (name "/P0.13") (class "Default")
      (node (ref "0.13") (pin "1") (pinfunction "1_1") (pintype "passive"))
      (node (ref "U1") (pin "AD8") (pinfunction "P0.13_AD8") (pintype "bidirectional"))
    )
    (net (code "19") (name "/P0.14") (class "Default")
      (node (ref "0.14") (pin "1") (pinfunction "1_1") (pintype "passive"))
      (node (ref "U1") (pin "AC9") (pinfunction "P0.14_AC9") (pintype "bidirectional"))
    )
    (net (code "20") (name "/P0.15") (class "Default")
      (node (ref "0.15") (pin "1") (pinfunction "1_1") (pintype "passive"))
      (node (ref "U1") (pin "AD10") (pinfunction "P0.15_AD10") (pintype "bidirectional"))
    )
    (net (code "21") (name "/P0.17") (class "Default")
      (node (ref "0.17") (pin "1") (pinfunction "1_1") (pintype "passive"))
      (node (ref "U1") (pin "AD12") (pinfunction "P0.17_AD12") (pintype "bidirectional"))
    )
    (net (code "22") (name "/P0.20") (class "Default")
      (node (ref "0.20") (pin "1") (pinfunction "1_1") (pintype "passive"))
      (node (ref "U1") (pin "AD16") (pinfunction "P0.20_AD16") (pintype "bidirectional"))
    )
    (net (code "23") (name "/P0.22") (class "Default")
      (node (ref "0.22") (pin "1") (pinfunction "1_1") (pintype "passive"))
      (node (ref "U1") (pin "AD18") (pinfunction "P0.22_AD18") (pintype "bidirectional"))
    )
    (net (code "24") (name "/P0.24") (class "Default")
      (node (ref "0.24") (pin "1") (pinfunction "1_1") (pintype "passive"))
      (node (ref "U1") (pin "AD20") (pinfunction "P0.24_AD20") (pintype "bidirectional"))
    )
    (net (code "25") (name "/P0.26") (class "Default")
      (node (ref "0.26") (pin "1") (pinfunction "1_1") (pintype "passive"))
      (node (ref "U1") (pin "G1") (pinfunction "P0.26_G1") (pintype "bidirectional"))
    )
    (net (code "26") (name "/P0.29") (class "Default")
      (node (ref "0.29") (pin "1") (pinfunction "1_1") (pintype "passive"))
      (node (ref "U1") (pin "A10") (pinfunction "P0.29/AIN5_A10") (pintype "bidirectional"))
    )
    (net (code "27") (name "/P0.31") (class "Default")
      (node (ref "0.31") (pin "1") (pinfunction "1_1") (pintype "passive"))
      (node (ref "U1") (pin "A8") (pinfunction "P0.31/AIN7_A8") (pintype "bidirectional"))
    )
    (net (code "28") (name "/P1.00") (class "Default")
      (node (ref "1.00") (pin "1") (pinfunction "1_1") (pintype "passive"))
      (node (ref "U1") (pin "AD22") (pinfunction "P1.00_AD22") (pintype "bidirectional"))
    )
    (net (code "29") (name "/P1.01") (class "Default")
      (node (ref "1.01") (pin "1") (pinfunction "1_1") (pintype "passive"))
      (node (ref "U1") (pin "Y23") (pinfunction "P1.01_Y23") (pintype "bidirectional"))
    )
    (net (code "30") (name "/P1.02") (class "Default")
      (node (ref "1.02") (pin "1") (pinfunction "1_1") (pintype "passive"))
      (node (ref "U1") (pin "W24") (pinfunction "P1.02_W24") (pintype "bidirectional"))
    )
    (net (code "31") (name "/P1.04") (class "Default")
      (node (ref "1.04") (pin "1") (pinfunction "1_1") (pintype "passive"))
      (node (ref "U1") (pin "U24") (pinfunction "P1.04_U24") (pintype "bidirectional"))
    )
    (net (code "32") (name "/P1.07") (class "Default")
      (node (ref "1.07") (pin "1") (pinfunction "1_1") (pintype "passive"))
      (node (ref "U1") (pin "P23") (pinfunction "P1.07_P23") (pintype "bidirectional"))
    )
    (net (code "33") (name "/P1.10") (class "Default")
      (node (ref "1.10") (pin "1") (pinfunction "1_1") (pintype "passive"))
      (node (ref "U1") (pin "A20") (pinfunction "P1.10_A20") (pintype "bidirectional"))
    )
    (net (code "34") (name "/P1.11") (class "Default")
      (node (ref "1.11") (pin "1") (pinfunction "1_1") (pintype "passive"))
      (node (ref "U1") (pin "B19") (pinfunction "P1.11_B19") (pintype "bidirectional"))
    )
    (net (code "35") (name "/P1.13") (class "Default")
      (node (ref "1.13") (pin "1") (pinfunction "1_1") (pintype "passive"))
      (node (ref "U1") (pin "A16") (pinfunction "P1.13_A16") (pintype "bidirectional"))
    )
    (net (code "36") (name "/P1.15") (class "Default")
      (node (ref "1.15") (pin "1") (pinfunction "1_1") (pintype "passive"))
      (node (ref "U1") (pin "A14") (pinfunction "P1.15_A14") (pintype "bidirectional"))
    )
    (net (code "37") (name "/RESET") (class "Default")
      (node (ref "C27") (pin "2") (pinfunction "2_2") (pintype "passive"))
      (node (ref "P1") (pin "10") (pinfunction "10_10") (pintype "passive"))
      (node (ref "R2") (pin "1") (pinfunction "1_1") (pintype "passive"))
      (node (ref "SW2") (pin "1") (pinfunction "N.O_1") (pintype "passive"))
      (node (ref "U1") (pin "AC13") (pinfunction "P0.18/RESET_AC13") (pintype "bidirectional"))
      (node (ref "U1") (pin "AC15") (pinfunction "P0.19_AC15") (pintype "bidirectional"))
      (node (ref "U1") (pin "AC17") (pinfunction "P0.21_AC17") (pintype "bidirectional"))
      (node (ref "U1") (pin "AC19") (pinfunction "P0.23_AC19") (pintype "bidirectional"))
      (node (ref "U1") (pin "AC21") (pinfunction "P0.25_AC21") (pintype "bidirectional"))
    )
    (net (code "38") (name "/RF") (class "Default")
      (node (ref "C25") (pin "1") (pinfunction "1_1") (pintype "passive"))
      (node (ref "C4") (pin "2") (pinfunction "2_2") (pintype "passive"))
      (node (ref "L1") (pin "2") (pinfunction "2_2") (pintype "passive"))
      (node (ref "R1") (pin "1") (pinfunction "1_1") (pintype "passive"))
    )
    (net (code "39") (name "/SW1") (class "Default")
      (node (ref "SW1") (pin "1") (pinfunction "N.O_1") (pintype "passive"))
      (node (ref "U1") (pin "R24") (pinfunction "P1.06_R24") (pintype "bidirectional"))
    )
    (net (code "40") (name "/SWDCLK") (class "Default")
      (node (ref "J2") (pin "4") (pinfunction "4_4") (pintype "passive"))
      (node (ref "P1") (pin "4") (pinfunction "4_4") (pintype "passive"))
      (node (ref "SWDCLK") (pin "1") (pinfunction "1_1") (pintype "passive"))
      (node (ref "U1") (pin "AA24") (pinfunction "SWDCLK_AA24") (pintype "input"))
    )
    (net (code "41") (name "/SWDIO") (class "Default")
      (node (ref "J2") (pin "2") (pinfunction "2_2") (pintype "passive"))
      (node (ref "P1") (pin "2") (pinfunction "2_2") (pintype "passive"))
      (node (ref "SWDIO") (pin "1") (pinfunction "1_1") (pintype "passive"))
      (node (ref "U1") (pin "AC24") (pinfunction "SWDIO_AC24") (pintype "bidirectional"))
    )
    (net (code "42") (name "/XC1") (class "Default")
      (node (ref "C1") (pin "1") (pinfunction "1_1") (pintype "passive"))
      (node (ref "U1") (pin "B24") (pinfunction "XC1_B24") (pintype "input"))
      (node (ref "X1") (pin "1") (pinfunction "IN_1") (pintype "passive"))
    )
    (net (code "43") (name "/XC2") (class "Default")
      (node (ref "C2") (pin "1") (pinfunction "1_1") (pintype "passive"))
      (node (ref "U1") (pin "A23") (pinfunction "XC2_A23") (pintype "output"))
      (node (ref "X1") (pin "3") (pinfunction "OUT_3") (pintype "passive"))
    )
    (net (code "44") (name "GND") (class "Default")
      (node (ref "C11") (pin "2") (pinfunction "2_2") (pintype "passive"))
      (node (ref "C12") (pin "2") (pinfunction "2_2") (pintype "passive"))
      (node (ref "C13") (pin "2") (pinfunction "2_2") (pintype "passive"))
      (node (ref "C14") (pin "2") (pinfunction "2_2") (pintype "passive"))
      (node (ref "C15") (pin "1") (pinfunction "1_1") (pintype "passive"))
      (node (ref "C16") (pin "2") (pinfunction "2_2") (pintype "passive"))
      (node (ref "C17") (pin "2") (pinfunction "2_2") (pintype "passive"))
      (node (ref "C18") (pin "2") (pinfunction "2_2") (pintype "passive"))
      (node (ref "C19") (pin "2") (pinfunction "2_2") (pintype "passive"))
      (node (ref "C2") (pin "2") (pinfunction "2_2") (pintype "passive"))
      (node (ref "C20") (pin "2") (pinfunction "2_2") (pintype "passive"))
      (node (ref "C21") (pin "1") (pinfunction "1_1") (pintype "passive"))
      (node (ref "C22") (pin "1") (pinfunction "1_1") (pintype "passive"))
      (node (ref "C23") (pin "1") (pinfunction "1_1") (pintype "passive"))
      (node (ref "C24") (pin "1") (pinfunction "1_1") (pintype "passive"))
      (node (ref "C25") (pin "2") (pinfunction "2_2") (pintype "passive"))
      (node (ref "C26") (pin "1") (pinfunction "1_1") (pintype "passive"))
      (node (ref "C27") (pin "1") (pinfunction "1_1") (pintype "passive"))
      (node (ref "C28") (pin "1") (pinfunction "1_1") (pintype "passive"))
      (node (ref "C29") (pin "2") (pinfunction "2_2") (pintype "passive"))
      (node (ref "C3") (pin "1") (pinfunction "1_1") (pintype "passive"))
      (node (ref "C4") (pin "1") (pinfunction "1_1") (pintype "passive"))
      (node (ref "C5") (pin "2") (pinfunction "2_2") (pintype "passive"))
      (node (ref "C6") (pin "2") (pinfunction "2_2") (pintype "passive"))
      (node (ref "C7") (pin "2") (pinfunction "2_2") (pintype "passive"))
      (node (ref "C8") (pin "2") (pinfunction "2_2") (pintype "passive"))
      (node (ref "C9") (pin "2") (pinfunction "2_2") (pintype "passive"))
      (node (ref "D1") (pin "1") (pinfunction "GND_1") (pintype "passive"))
      (node (ref "FB2") (pin "2") (pinfunction "2_2") (pintype "passive"))
      (node (ref "GND1") (pin "1") (pinfunction "1_1") (pintype "passive"))
      (node (ref "GND2") (pin "1") (pinfunction "1_1") (pintype "passive"))
      (node (ref "GND3") (pin "1") (pinfunction "1_1") (pintype "passive"))
      (node (ref "GND4") (pin "1") (pinfunction "1_1") (pintype "passive"))
      (node (ref "J2") (pin "3") (pinfunction "3_3") (pintype "passive"))
      (node (ref "P1") (pin "3") (pinfunction "3_3") (pintype "passive"))
      (node (ref "P1") (pin "5") (pinfunction "5_5") (pintype "passive"))
      (node (ref "P1") (pin "9") (pinfunction "9_9") (pintype "passive"))
      (node (ref "SW1") (pin "2") (pinfunction "COM_2") (pintype "passive"))
      (node (ref "SW2") (pin "2") (pinfunction "COM_2") (pintype "passive"))
      (node (ref "U1") (pin "74") (pinfunction "GND_74") (pintype "power_in"))
      (node (ref "U1") (pin "B15") (pinfunction "P1.14_B15") (pintype "bidirectional"))
      (node (ref "U1") (pin "B7") (pinfunction "VSS_B7") (pintype "power_in"))
      (node (ref "U1") (pin "F23") (pinfunction "VSS_PA_F23") (pintype "power_in"))
      (node (ref "X1") (pin "2") (pinfunction "GND_2") (pintype "passive"))
    )
    (net (code "45") (name "Net-(C1-Pad2)") (class "Default")
      (node (ref "C1") (pin "2") (pinfunction "2_2") (pintype "passive"))
      (node (ref "X1") (pin "4") (pinfunction "GND_4") (pintype "passive"))
    )
    (net (code "46") (name "Net-(J1-D+)") (class "Default")
      (node (ref "D+") (pin "1") (pinfunction "1_1") (pintype "passive"))
      (node (ref "J1") (pin "3") (pinfunction "D+_3") (pintype "passive"))
      (node (ref "SB4") (pin "2") (pinfunction "1_2") (pintype "passive"))
    )
    (net (code "47") (name "Net-(J1-D-)") (class "Default")
      (node (ref "D-") (pin "1") (pinfunction "1_1") (pintype "passive"))
      (node (ref "J1") (pin "2") (pinfunction "D-_2") (pintype "passive"))
      (node (ref "SB3") (pin "2") (pinfunction "1_2") (pintype "passive"))
    )
    (net (code "48") (name "Net-(J1-GND)") (class "Default")
      (node (ref "FB2") (pin "1") (pinfunction "1_1") (pintype "passive"))
      (node (ref "J1") (pin "4") (pinfunction "GND_4") (pintype "passive"))
      (node (ref "UGND") (pin "1") (pinfunction "1_1") (pintype "passive"))
    )
    (net (code "49") (name "Net-(L2-Pad1)") (class "Default")
      (node (ref "L2") (pin "1") (pinfunction "1_1") (pintype "passive"))
      (node (ref "L3") (pin "2") (pinfunction "2_2") (pintype "passive"))
    )
    (net (code "50") (name "Net-(LD1-C)") (class "Default")
      (node (ref "LD1") (pin "1") (pinfunction "C_1") (pintype "passive"))
      (node (ref "R3") (pin "2") (pinfunction "2_2") (pintype "passive"))
    )
    (net (code "51") (name "Net-(LD2-C_BLUE)") (class "Default")
      (node (ref "LD2") (pin "3") (pinfunction "C_BLUE_3") (pintype "passive"))
      (node (ref "R6") (pin "2") (pinfunction "2_2") (pintype "passive"))
    )
    (net (code "52") (name "Net-(LD2-C_GREEN)") (class "Default")
      (node (ref "LD2") (pin "2") (pinfunction "C_GREEN_2") (pintype "passive"))
      (node (ref "R5") (pin "2") (pinfunction "2_2") (pintype "passive"))
    )
    (net (code "53") (name "Net-(LD2-C_RED)") (class "Default")
      (node (ref "LD2") (pin "1") (pinfunction "C_RED_1") (pintype "passive"))
      (node (ref "R4") (pin "2") (pinfunction "2_2") (pintype "passive"))
    )
    (net (code "54") (name "Net-(SB1-1)") (class "Default")
      (node (ref "SB1") (pin "2") (pinfunction "1_2") (pintype "passive"))
      (node (ref "SB2") (pin "1") (pinfunction "0_1") (pintype "passive"))
      (node (ref "U1") (pin "Y2") (pinfunction "VDDH_Y2") (pintype "power_in"))
    )
    (net (code "55") (name "Net-(U1-ANT)") (class "Default")
      (node (ref "C3") (pin "2") (pinfunction "2_2") (pintype "passive"))
      (node (ref "L1") (pin "1") (pinfunction "1_1") (pintype "passive"))
      (node (ref "U1") (pin "H23") (pinfunction "ANT_H23") (pintype "bidirectional"))
    )
    (net (code "56") (name "Net-(U1-DCC)") (class "Default")
      (node (ref "L2") (pin "2") (pinfunction "2_2") (pintype "passive"))
      (node (ref "U1") (pin "B3") (pinfunction "DCC_B3") (pintype "output"))
    )
    (net (code "57") (name "Net-(U1-DCCH)") (class "Default")
      (node (ref "L4") (pin "2") (pinfunction "2_2") (pintype "passive"))
      (node (ref "U1") (pin "AB2") (pinfunction "DCCH_AB2") (pintype "power_in"))
    )
    (net (code "58") (name "Net-(U1-DEC2)") (class "Default")
      (node (ref "C13") (pin "1") (pinfunction "1_1") (pintype "passive"))
      (node (ref "U1") (pin "A18") (pinfunction "DEC2_A18") (pintype "power_in"))
    )
    (net (code "59") (name "Net-(U1-DEC5)") (class "Default")
      (node (ref "C9") (pin "1") (pinfunction "1_1") (pintype "passive"))
      (node (ref "U1") (pin "N24") (pinfunction "DEC5_N24") (pintype "power_in"))
    )
    (net (code "60") (name "Net-(U1-DECUSB)") (class "Default")
      (node (ref "C20") (pin "1") (pinfunction "1_1") (pintype "passive"))
      (node (ref "U1") (pin "AC5") (pinfunction "DECUSB_AC5") (pintype "power_in"))
    )
    (net (code "61") (name "VBUS") (class "Default")
      (node (ref "C22") (pin "2") (pinfunction "2_2") (pintype "passive"))
      (node (ref "FB1") (pin "2") (pinfunction "2_2") (pintype "passive"))
      (node (ref "R7") (pin "2") (pinfunction "2_2") (pintype "passive"))
    )
    (net (code "62") (name "VBUS'") (class "Default")
      (node (ref "C21") (pin "2") (pinfunction "2_2") (pintype "passive"))
      (node (ref "C23") (pin "2") (pinfunction "2_2") (pintype "passive"))
      (node (ref "C24") (pin "2") (pinfunction "2_2") (pintype "passive"))
      (node (ref "D1") (pin "4") (pinfunction "VCC_4") (pintype "passive"))
      (node (ref "FB1") (pin "1") (pinfunction "1_1") (pintype "passive"))
      (node (ref "J1") (pin "1") (pinfunction "VBUS_1") (pintype "passive"))
      (node (ref "J2") (pin "5") (pinfunction "5_5") (pintype "passive"))
      (node (ref "VBUS1") (pin "1") (pinfunction "1_1") (pintype "passive"))
      (node (ref "VBUS2") (pin "1") (pinfunction "1_1") (pintype "passive"))
    )
    (net (code "63") (name "VBUS_nRF") (class "Default")
      (node (ref "C19") (pin "1") (pinfunction "1_1") (pintype "passive"))
      (node (ref "R7") (pin "1") (pinfunction "1_1") (pintype "passive"))
      (node (ref "SB2") (pin "2") (pinfunction "1_2") (pintype "passive"))
      (node (ref "U1") (pin "AD2") (pinfunction "VBUS_AD2") (pintype "power_in"))
    )
    (net (code "64") (name "VDD_nRF") (class "Default")
      (node (ref "C12") (pin "1") (pinfunction "1_1") (pintype "passive"))
      (node (ref "C14") (pin "1") (pinfunction "1_1") (pintype "passive"))
      (node (ref "C6") (pin "1") (pinfunction "1_1") (pintype "passive"))
      (node (ref "C7") (pin "1") (pinfunction "1_1") (pintype "passive"))
      (node (ref "C8") (pin "1") (pinfunction "1_1") (pintype "passive"))
      (node (ref "J2") (pin "1") (pinfunction "1_1") (pintype "passive"))
      (node (ref "L4") (pin "1") (pinfunction "1_1") (pintype "passive"))
      (node (ref "LD1") (pin "2") (pinfunction "A_2") (pintype "passive"))
      (node (ref "LD2") (pin "4") (pinfunction "A_4") (pintype "passive"))
      (node (ref "P1") (pin "1") (pinfunction "1_1") (pintype "passive"))
      (node (ref "R2") (pin "2") (pinfunction "2_2") (pintype "passive"))
      (node (ref "SB1") (pin "1") (pinfunction "0_1") (pintype "passive"))
      (node (ref "U1") (pin "A22") (pinfunction "VDD_A22") (pintype "power_in"))
      (node (ref "U1") (pin "AD14") (pinfunction "VDD_AD14") (pintype "power_in"))
      (node (ref "U1") (pin "AD23") (pinfunction "VDD_AD23") (pintype "power_in"))
      (node (ref "U1") (pin "B1") (pinfunction "VDD_B1") (pintype "power_in"))
      (node (ref "U1") (pin "W1") (pinfunction "VDD_W1") (pintype "power_in"))
      (node (ref "VDD OUT") (pin "1") (pinfunction "1_1") (pintype "passive"))
      (node (ref "VDD nRF") (pin "1") (pinfunction "1_1") (pintype "passive"))
    )
    (net (code "65") (name "unconnected-(J2-Pad6)") (class "Default")
      (node (ref "J2") (pin "6") (pinfunction "6_6") (pintype "passive"))
    )
    (net (code "66") (name "unconnected-(J2-Pad7)") (class "Default")
      (node (ref "J2") (pin "7") (pinfunction "7_7") (pintype "passive"))
    )
    (net (code "67") (name "unconnected-(J2-Pad8)") (class "Default")
      (node (ref "J2") (pin "8") (pinfunction "8_8") (pintype "passive"))
    )
    (net (code "68") (name "unconnected-(J2-Pad9)") (class "Default")
      (node (ref "J2") (pin "9") (pinfunction "9_9") (pintype "passive"))
    )
    (net (code "69") (name "unconnected-(J2-Pad10)") (class "Default")
      (node (ref "J2") (pin "10") (pinfunction "10_10") (pintype "passive"))
    )
    (net (code "70") (name "unconnected-(P1-Pad6)") (class "Default")
      (node (ref "P1") (pin "6") (pinfunction "6_6") (pintype "passive"))
    )
    (net (code "71") (name "unconnected-(P1-Pad7)") (class "Default")
      (node (ref "P1") (pin "7") (pinfunction "7_7") (pintype "passive"))
    )
    (net (code "72") (name "unconnected-(P1-Pad8)") (class "Default")
      (node (ref "P1") (pin "8") (pinfunction "8_8") (pintype "passive"))
    )
    (net (code "73") (name "unconnected-(U1-P0.03{slash}AIN1-PadB13)") (class "Default")
      (node (ref "U1") (pin "B13") (pinfunction "P0.03/AIN1_B13") (pintype "bidirectional"))
    )
    (net (code "74") (name "unconnected-(U1-P0.05{slash}AIN3-PadK2)") (class "Default")
      (node (ref "U1") (pin "K2") (pinfunction "P0.05/AIN3_K2") (pintype "bidirectional"))
    )
    (net (code "75") (name "unconnected-(U1-P0.07-PadM2)") (class "Default")
      (node (ref "U1") (pin "M2") (pinfunction "P0.07_M2") (pintype "bidirectional"))
    )
    (net (code "76") (name "unconnected-(U1-P0.16-PadAC11)") (class "Default")
      (node (ref "U1") (pin "AC11") (pinfunction "P0.16_AC11") (pintype "bidirectional"))
    )
    (net (code "77") (name "unconnected-(U1-P0.27-PadH2)") (class "Default")
      (node (ref "U1") (pin "H2") (pinfunction "P0.27_H2") (pintype "bidirectional"))
    )
    (net (code "78") (name "unconnected-(U1-P0.28{slash}AIN4-PadB11)") (class "Default")
      (node (ref "U1") (pin "B11") (pinfunction "P0.28/AIN4_B11") (pintype "bidirectional"))
    )
    (net (code "79") (name "unconnected-(U1-P0.30{slash}AIN6-PadB9)") (class "Default")
      (node (ref "U1") (pin "B9") (pinfunction "P0.30/AIN6_B9") (pintype "bidirectional"))
    )
    (net (code "80") (name "unconnected-(U1-P1.03-PadV23)") (class "Default")
      (node (ref "U1") (pin "V23") (pinfunction "P1.03_V23") (pintype "bidirectional"))
    )
    (net (code "81") (name "unconnected-(U1-P1.05-PadT23)") (class "Default")
      (node (ref "U1") (pin "T23") (pinfunction "P1.05_T23") (pintype "bidirectional"))
    )
    (net (code "82") (name "unconnected-(U1-P1.08-PadP2)") (class "Default")
      (node (ref "U1") (pin "P2") (pinfunction "P1.08_P2") (pintype "bidirectional"))
    )
    (net (code "83") (name "unconnected-(U1-P1.12-PadB17)") (class "Default")
      (node (ref "U1") (pin "B17") (pinfunction "P1.12_B17") (pintype "bidirectional"))
    )
  )
)
